# cpu.net
KiCad netlist of a schematic drawn in Altium Designer
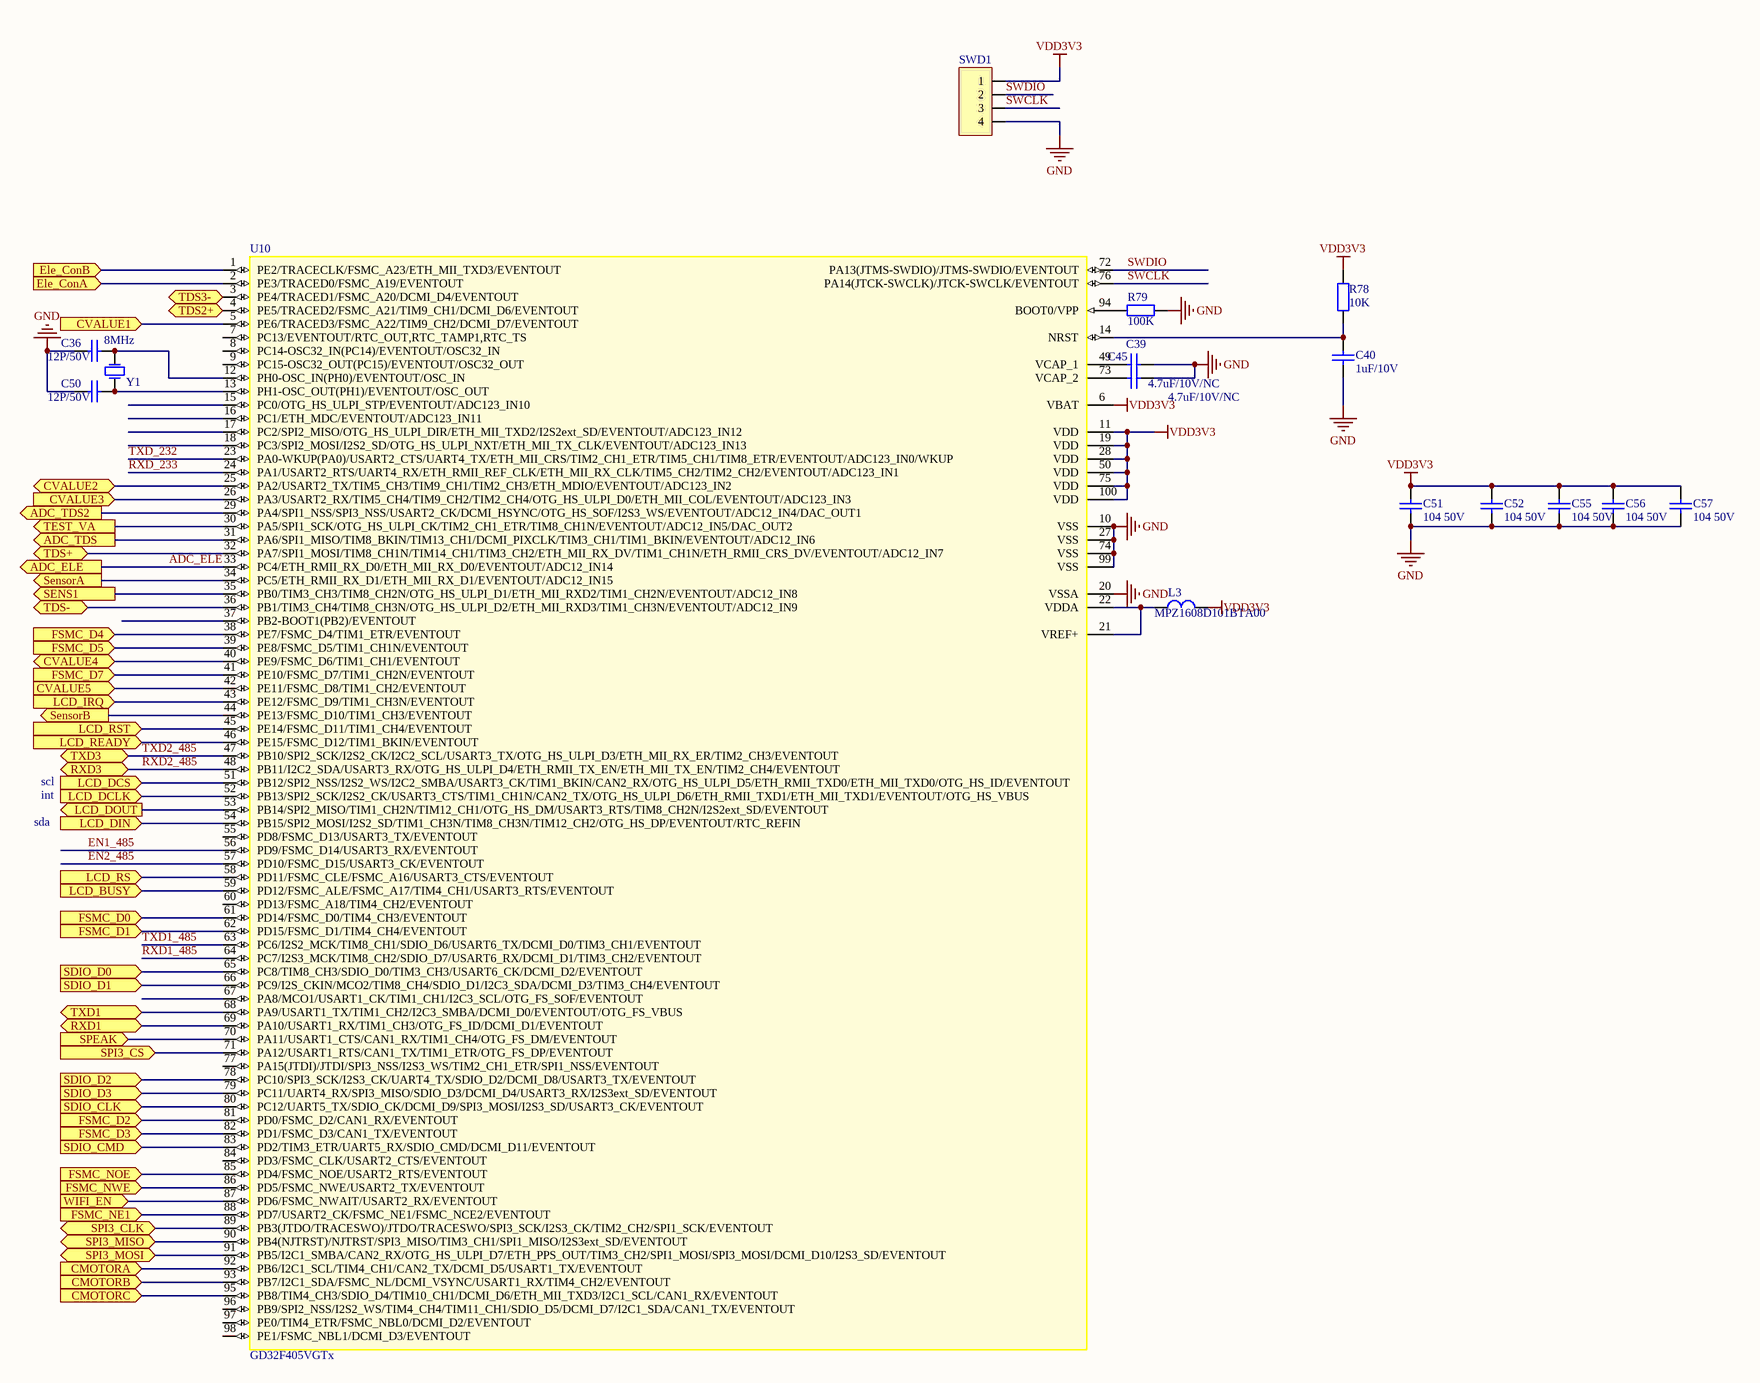
[diagram p0: cpu.SchDoc]

(export (version "E")
  (design (tool "Eeschema 10.0.6"))
  (components
    (comp (ref "C36")
      (value "12P/50V")
      (footprint "SMD-0603C")
      (description "贴片电容 5%")
      (libsource (lib "XiaoyI") (part "CAP4"))
    )
    (comp (ref "C39")
      (value "4.7uF/10V/NC")
      (footprint "SMD-0603C")
      (description "贴片电容 20%")
      (libsource (lib "XiaoyI") (part "CAP4"))
    )
    (comp (ref "C40")
      (value "1uF/10V")
      (footprint "SMD-0603C")
      (description "贴片电容 20%")
      (libsource (lib "XiaoyI") (part "CAP4"))
    )
    (comp (ref "C45")
      (value "4.7uF/10V/NC")
      (footprint "SMD-0603C")
      (description "贴片电容 20%")
      (libsource (lib "XiaoyI") (part "CAP4"))
    )
    (comp (ref "C50")
      (value "12P/50V")
      (footprint "SMD-0603C")
      (description "贴片电容 5%")
      (libsource (lib "XiaoyI") (part "CAP4"))
    )
    (comp (ref "C51")
      (value "104 50V")
      (footprint "SMD-0603C")
      (description "贴片电容 20%")
      (libsource (lib "XiaoyI") (part "CAP4"))
    )
    (comp (ref "C52")
      (value "104 50V")
      (footprint "SMD-0603C")
      (description "贴片电容 20%")
      (libsource (lib "XiaoyI") (part "CAP4"))
    )
    (comp (ref "C55")
      (value "104 50V")
      (footprint "SMD-0603C")
      (description "贴片电容 20%")
      (libsource (lib "XiaoyI") (part "CAP4"))
    )
    (comp (ref "C56")
      (value "104 50V")
      (footprint "SMD-0603C")
      (description "贴片电容 20%")
      (libsource (lib "XiaoyI") (part "CAP4"))
    )
    (comp (ref "C57")
      (value "104 50V")
      (footprint "SMD-0603C")
      (description "贴片电容 20%")
      (libsource (lib "XiaoyI") (part "CAP4"))
    )
    (comp (ref "L3")
      (value "MPZ1608D101BTA00")
      (footprint "SMD-0603")
      (description "磁珠电感 100R 100MHz")
      (libsource (lib "XiaoyI") (part "CIZHU1"))
    )
    (comp (ref "R78")
      (value "10K")
      (footprint "SMD-0603")
      (description "贴片电阻 5%")
      (libsource (lib "") (part "RES2_1"))
    )
    (comp (ref "R79")
      (value "100K")
      (footprint "SMD-0603")
      (description "贴片电阻 5%")
      (libsource (lib "XiaoyI") (part "RES2"))
    )
    (comp (ref "SWD1")
      (value "SIP-4 (NC)")
      (footprint "SIP-4")
      (description "ISP 下载")
      (libsource (lib "XiaoyI") (part "SIP-4"))
    )
    (comp (ref "U10")
      (value "GD32F405VGTx")
      (footprint "STM-LQFP100_N")
      (fields (field (name "MANUFACTURER") "STMicroelectronics") (field (name "PARTNUMBER") "STM32F405VGT6"))
      (libsource (lib "STM32F4") (part "STM32F405VGTx"))
    )
    (comp (ref "Y1")
      (value "8MHz")
      (footprint "XTAL-3225-2")
      (description "3225 贴片晶振")
      (libsource (lib "XiaoyI") (part "XTAL"))
    )
  )
  (nets
    (net (code "1") (name "/ADC_ELE") (class "Default")
      (node (ref "U10") (pin "33") (pinfunction "PC4/ETH_RMII_RX_D0/ETH_MII_RX_D0/EVENTOUT/ADC12_IN14_33") (pintype "bidirectional"))
    )
    (net (code "2") (name "/ADC_TDS") (class "Default")
      (node (ref "U10") (pin "31") (pinfunction "PA6/SPI1_MISO/TIM8_BKIN/TIM13_CH1/DCMI_PIXCLK/TIM3_CH1/TIM1_BKIN/EVENTOUT/ADC12_IN6_31") (pintype "bidirectional"))
    )
    (net (code "3") (name "/ADC_TDS2") (class "Default")
      (node (ref "U10") (pin "29") (pinfunction "PA4/SPI1_NSS/SPI3_NSS/USART2_CK/DCMI_HSYNC/OTG_HS_SOF/I2S3_WS/EVENTOUT/ADC12_IN4/DAC_OUT1_29") (pintype "bidirectional"))
    )
    (net (code "4") (name "/CMOTORA") (class "Default")
      (node (ref "U10") (pin "92") (pinfunction "PB6/I2C1_SCL/TIM4_CH1/CAN2_TX/DCMI_D5/USART1_TX/EVENTOUT_92") (pintype "bidirectional"))
    )
    (net (code "5") (name "/CMOTORB") (class "Default")
      (node (ref "U10") (pin "93") (pinfunction "PB7/I2C1_SDA/FSMC_NL/DCMI_VSYNC/USART1_RX/TIM4_CH2/EVENTOUT_93") (pintype "bidirectional"))
    )
    (net (code "6") (name "/CMOTORC") (class "Default")
      (node (ref "U10") (pin "95") (pinfunction "PB8/TIM4_CH3/SDIO_D4/TIM10_CH1/DCMI_D6/ETH_MII_TXD3/I2C1_SCL/CAN1_RX/EVENTOUT_95") (pintype "bidirectional"))
    )
    (net (code "7") (name "/CVALUE1") (class "Default")
      (node (ref "U10") (pin "5") (pinfunction "PE6/TRACED3/FSMC_A22/TIM9_CH2/DCMI_D7/EVENTOUT_5") (pintype "bidirectional"))
    )
    (net (code "8") (name "/CVALUE2") (class "Default")
      (node (ref "U10") (pin "25") (pinfunction "PA2/USART2_TX/TIM5_CH3/TIM9_CH1/TIM2_CH3/ETH_MDIO/EVENTOUT/ADC123_IN2_25") (pintype "bidirectional"))
    )
    (net (code "9") (name "/CVALUE3") (class "Default")
      (node (ref "U10") (pin "26") (pinfunction "PA3/USART2_RX/TIM5_CH4/TIM9_CH2/TIM2_CH4/OTG_HS_ULPI_D0/ETH_MII_COL/EVENTOUT/ADC123_IN3_26") (pintype "bidirectional"))
    )
    (net (code "10") (name "/CVALUE4") (class "Default")
      (node (ref "U10") (pin "40") (pinfunction "PE9/FSMC_D6/TIM1_CH1/EVENTOUT_40") (pintype "bidirectional"))
    )
    (net (code "11") (name "/CVALUE5") (class "Default")
      (node (ref "U10") (pin "42") (pinfunction "PE11/FSMC_D8/TIM1_CH2/EVENTOUT_42") (pintype "bidirectional"))
    )
    (net (code "12") (name "/EN1_485") (class "Default")
      (node (ref "U10") (pin "56") (pinfunction "PD9/FSMC_D14/USART3_RX/EVENTOUT_56") (pintype "bidirectional"))
    )
    (net (code "13") (name "/EN2_485") (class "Default")
      (node (ref "U10") (pin "57") (pinfunction "PD10/FSMC_D15/USART3_CK/EVENTOUT_57") (pintype "bidirectional"))
    )
    (net (code "14") (name "/Ele_ConA") (class "Default")
      (node (ref "U10") (pin "2") (pinfunction "PE3/TRACED0/FSMC_A19/EVENTOUT_2") (pintype "bidirectional"))
    )
    (net (code "15") (name "/Ele_ConB") (class "Default")
      (node (ref "U10") (pin "1") (pinfunction "PE2/TRACECLK/FSMC_A23/ETH_MII_TXD3/EVENTOUT_1") (pintype "bidirectional"))
    )
    (net (code "16") (name "/FSMC_D0") (class "Default")
      (node (ref "U10") (pin "61") (pinfunction "PD14/FSMC_D0/TIM4_CH3/EVENTOUT_61") (pintype "bidirectional"))
    )
    (net (code "17") (name "/FSMC_D1") (class "Default")
      (node (ref "U10") (pin "62") (pinfunction "PD15/FSMC_D1/TIM4_CH4/EVENTOUT_62") (pintype "bidirectional"))
    )
    (net (code "18") (name "/FSMC_D2") (class "Default")
      (node (ref "U10") (pin "81") (pinfunction "PD0/FSMC_D2/CAN1_RX/EVENTOUT_81") (pintype "bidirectional"))
    )
    (net (code "19") (name "/FSMC_D3") (class "Default")
      (node (ref "U10") (pin "82") (pinfunction "PD1/FSMC_D3/CAN1_TX/EVENTOUT_82") (pintype "bidirectional"))
    )
    (net (code "20") (name "/FSMC_D4") (class "Default")
      (node (ref "U10") (pin "38") (pinfunction "PE7/FSMC_D4/TIM1_ETR/EVENTOUT_38") (pintype "bidirectional"))
    )
    (net (code "21") (name "/FSMC_D5") (class "Default")
      (node (ref "U10") (pin "39") (pinfunction "PE8/FSMC_D5/TIM1_CH1N/EVENTOUT_39") (pintype "bidirectional"))
    )
    (net (code "22") (name "/FSMC_D7") (class "Default")
      (node (ref "U10") (pin "41") (pinfunction "PE10/FSMC_D7/TIM1_CH2N/EVENTOUT_41") (pintype "bidirectional"))
    )
    (net (code "23") (name "/FSMC_NE1") (class "Default")
      (node (ref "U10") (pin "88") (pinfunction "PD7/USART2_CK/FSMC_NE1/FSMC_NCE2/EVENTOUT_88") (pintype "bidirectional"))
    )
    (net (code "24") (name "/FSMC_NOE") (class "Default")
      (node (ref "U10") (pin "85") (pinfunction "PD4/FSMC_NOE/USART2_RTS/EVENTOUT_85") (pintype "bidirectional"))
    )
    (net (code "25") (name "/FSMC_NWE") (class "Default")
      (node (ref "U10") (pin "86") (pinfunction "PD5/FSMC_NWE/USART2_TX/EVENTOUT_86") (pintype "bidirectional"))
    )
    (net (code "26") (name "/LCD_BUSY") (class "Default")
      (node (ref "U10") (pin "59") (pinfunction "PD12/FSMC_ALE/FSMC_A17/TIM4_CH1/USART3_RTS/EVENTOUT_59") (pintype "bidirectional"))
    )
    (net (code "27") (name "/LCD_DCLK") (class "Default")
      (node (ref "U10") (pin "52") (pinfunction "PB13/SPI2_SCK/I2S2_CK/USART3_CTS/TIM1_CH1N/CAN2_TX/OTG_HS_ULPI_D6/ETH_RMII_TXD1/ETH_MII_TXD1/EVENTOUT/OTG_HS_VBUS_52") (pintype "bidirectional"))
    )
    (net (code "28") (name "/LCD_DCS") (class "Default")
      (node (ref "U10") (pin "51") (pinfunction "PB12/SPI2_NSS/I2S2_WS/I2C2_SMBA/USART3_CK/TIM1_BKIN/CAN2_RX/OTG_HS_ULPI_D5/ETH_RMII_TXD0/ETH_MII_TXD0/OTG_HS_ID/EVENTOUT_51") (pintype "bidirectional"))
    )
    (net (code "29") (name "/LCD_DIN") (class "Default")
      (node (ref "U10") (pin "54") (pinfunction "PB15/SPI2_MOSI/I2S2_SD/TIM1_CH3N/TIM8_CH3N/TIM12_CH2/OTG_HS_DP/EVENTOUT/RTC_REFIN_54") (pintype "bidirectional"))
    )
    (net (code "30") (name "/LCD_DOUT") (class "Default")
      (node (ref "U10") (pin "53") (pinfunction "PB14/SPI2_MISO/TIM1_CH2N/TIM12_CH1/OTG_HS_DM/USART3_RTS/TIM8_CH2N/I2S2ext_SD/EVENTOUT_53") (pintype "bidirectional"))
    )
    (net (code "31") (name "/LCD_IRQ") (class "Default")
      (node (ref "U10") (pin "43") (pinfunction "PE12/FSMC_D9/TIM1_CH3N/EVENTOUT_43") (pintype "bidirectional"))
    )
    (net (code "32") (name "/LCD_READY") (class "Default")
      (node (ref "U10") (pin "46") (pinfunction "PE15/FSMC_D12/TIM1_BKIN/EVENTOUT_46") (pintype "bidirectional"))
    )
    (net (code "33") (name "/LCD_RS") (class "Default")
      (node (ref "U10") (pin "58") (pinfunction "PD11/FSMC_CLE/FSMC_A16/USART3_CTS/EVENTOUT_58") (pintype "bidirectional"))
    )
    (net (code "34") (name "/LCD_RST") (class "Default")
      (node (ref "U10") (pin "45") (pinfunction "PE14/FSMC_D11/TIM1_CH4/EVENTOUT_45") (pintype "bidirectional"))
    )
    (net (code "35") (name "/RXD1") (class "Default")
      (node (ref "U10") (pin "69") (pinfunction "PA10/USART1_RX/TIM1_CH3/OTG_FS_ID/DCMI_D1/EVENTOUT_69") (pintype "bidirectional"))
    )
    (net (code "36") (name "/RXD1_485") (class "Default")
      (node (ref "U10") (pin "64") (pinfunction "PC7/I2S3_MCK/TIM8_CH2/SDIO_D7/USART6_RX/DCMI_D1/TIM3_CH2/EVENTOUT_64") (pintype "bidirectional"))
    )
    (net (code "37") (name "/RXD2_485") (class "Default")
      (node (ref "U10") (pin "48") (pinfunction "PB11/I2C2_SDA/USART3_RX/OTG_HS_ULPI_D4/ETH_RMII_TX_EN/ETH_MII_TX_EN/TIM2_CH4/EVENTOUT_48") (pintype "bidirectional"))
    )
    (net (code "38") (name "/RXD_233") (class "Default")
      (node (ref "U10") (pin "24") (pinfunction "PA1/USART2_RTS/UART4_RX/ETH_RMII_REF_CLK/ETH_MII_RX_CLK/TIM5_CH2/TIM2_CH2/EVENTOUT/ADC123_IN1_24") (pintype "bidirectional"))
    )
    (net (code "39") (name "/SDIO_CLK") (class "Default")
      (node (ref "U10") (pin "80") (pinfunction "PC12/UART5_TX/SDIO_CK/DCMI_D9/SPI3_MOSI/I2S3_SD/USART3_CK/EVENTOUT_80") (pintype "bidirectional"))
    )
    (net (code "40") (name "/SDIO_CMD") (class "Default")
      (node (ref "U10") (pin "83") (pinfunction "PD2/TIM3_ETR/UART5_RX/SDIO_CMD/DCMI_D11/EVENTOUT_83") (pintype "bidirectional"))
    )
    (net (code "41") (name "/SDIO_D0") (class "Default")
      (node (ref "U10") (pin "65") (pinfunction "PC8/TIM8_CH3/SDIO_D0/TIM3_CH3/USART6_CK/DCMI_D2/EVENTOUT_65") (pintype "bidirectional"))
    )
    (net (code "42") (name "/SDIO_D1") (class "Default")
      (node (ref "U10") (pin "66") (pinfunction "PC9/I2S_CKIN/MCO2/TIM8_CH4/SDIO_D1/I2C3_SDA/DCMI_D3/TIM3_CH4/EVENTOUT_66") (pintype "bidirectional"))
    )
    (net (code "43") (name "/SDIO_D2") (class "Default")
      (node (ref "U10") (pin "78") (pinfunction "PC10/SPI3_SCK/I2S3_CK/UART4_TX/SDIO_D2/DCMI_D8/USART3_TX/EVENTOUT_78") (pintype "bidirectional"))
    )
    (net (code "44") (name "/SDIO_D3") (class "Default")
      (node (ref "U10") (pin "79") (pinfunction "PC11/UART4_RX/SPI3_MISO/SDIO_D3/DCMI_D4/USART3_RX/I2S3ext_SD/EVENTOUT_79") (pintype "bidirectional"))
    )
    (net (code "45") (name "/SENS1") (class "Default")
      (node (ref "U10") (pin "35") (pinfunction "PB0/TIM3_CH3/TIM8_CH2N/OTG_HS_ULPI_D1/ETH_MII_RXD2/TIM1_CH2N/EVENTOUT/ADC12_IN8_35") (pintype "bidirectional"))
    )
    (net (code "46") (name "/SPEAK") (class "Default")
      (node (ref "U10") (pin "70") (pinfunction "PA11/USART1_CTS/CAN1_RX/TIM1_CH4/OTG_FS_DM/EVENTOUT_70") (pintype "bidirectional"))
    )
    (net (code "47") (name "/SPI3_CLK") (class "Default")
      (node (ref "U10") (pin "89") (pinfunction "PB3(JTDO/TRACESWO)/JTDO/TRACESWO/SPI3_SCK/I2S3_CK/TIM2_CH2/SPI1_SCK/EVENTOUT_89") (pintype "bidirectional"))
    )
    (net (code "48") (name "/SPI3_CS") (class "Default")
      (node (ref "U10") (pin "71") (pinfunction "PA12/USART1_RTS/CAN1_TX/TIM1_ETR/OTG_FS_DP/EVENTOUT_71") (pintype "bidirectional"))
    )
    (net (code "49") (name "/SPI3_MISO") (class "Default")
      (node (ref "U10") (pin "90") (pinfunction "PB4(NJTRST)/NJTRST/SPI3_MISO/TIM3_CH1/SPI1_MISO/I2S3ext_SD/EVENTOUT_90") (pintype "bidirectional"))
    )
    (net (code "50") (name "/SPI3_MOSI") (class "Default")
      (node (ref "U10") (pin "91") (pinfunction "PB5/I2C1_SMBA/CAN2_RX/OTG_HS_ULPI_D7/ETH_PPS_OUT/TIM3_CH2/SPI1_MOSI/SPI3_MOSI/DCMI_D10/I2S3_SD/EVENTOUT_91") (pintype "bidirectional"))
    )
    (net (code "51") (name "/SWCLK") (class "Default")
      (node (ref "SWD1") (pin "3") (pinfunction "3_3") (pintype "passive"))
      (node (ref "U10") (pin "76") (pinfunction "PA14(JTCK-SWCLK)/JTCK-SWCLK/EVENTOUT_76") (pintype "bidirectional"))
    )
    (net (code "52") (name "/SWDIO") (class "Default")
      (node (ref "SWD1") (pin "2") (pinfunction "2_2") (pintype "passive"))
      (node (ref "U10") (pin "72") (pinfunction "PA13(JTMS-SWDIO)/JTMS-SWDIO/EVENTOUT_72") (pintype "bidirectional"))
    )
    (net (code "53") (name "/SensorA") (class "Default")
      (node (ref "U10") (pin "34") (pinfunction "PC5/ETH_RMII_RX_D1/ETH_MII_RX_D1/EVENTOUT/ADC12_IN15_34") (pintype "bidirectional"))
    )
    (net (code "54") (name "/SensorB") (class "Default")
      (node (ref "U10") (pin "44") (pinfunction "PE13/FSMC_D10/TIM1_CH3/EVENTOUT_44") (pintype "bidirectional"))
    )
    (net (code "55") (name "/TDS+") (class "Default")
      (node (ref "U10") (pin "32") (pinfunction "PA7/SPI1_MOSI/TIM8_CH1N/TIM14_CH1/TIM3_CH2/ETH_MII_RX_DV/TIM1_CH1N/ETH_RMII_CRS_DV/EVENTOUT/ADC12_IN7_32") (pintype "bidirectional"))
    )
    (net (code "56") (name "/TDS-") (class "Default")
      (node (ref "U10") (pin "36") (pinfunction "PB1/TIM3_CH4/TIM8_CH3N/OTG_HS_ULPI_D2/ETH_MII_RXD3/TIM1_CH3N/EVENTOUT/ADC12_IN9_36") (pintype "bidirectional"))
    )
    (net (code "57") (name "/TDS2+") (class "Default")
      (node (ref "U10") (pin "4") (pinfunction "PE5/TRACED2/FSMC_A21/TIM9_CH1/DCMI_D6/EVENTOUT_4") (pintype "bidirectional"))
    )
    (net (code "58") (name "/TDS3-") (class "Default")
      (node (ref "U10") (pin "3") (pinfunction "PE4/TRACED1/FSMC_A20/DCMI_D4/EVENTOUT_3") (pintype "bidirectional"))
    )
    (net (code "59") (name "/TEST_VA") (class "Default")
      (node (ref "U10") (pin "30") (pinfunction "PA5/SPI1_SCK/OTG_HS_ULPI_CK/TIM2_CH1_ETR/TIM8_CH1N/EVENTOUT/ADC12_IN5/DAC_OUT2_30") (pintype "bidirectional"))
    )
    (net (code "60") (name "/TXD1") (class "Default")
      (node (ref "U10") (pin "68") (pinfunction "PA9/USART1_TX/TIM1_CH2/I2C3_SMBA/DCMI_D0/EVENTOUT/OTG_FS_VBUS_68") (pintype "bidirectional"))
    )
    (net (code "61") (name "/TXD1_485") (class "Default")
      (node (ref "U10") (pin "63") (pinfunction "PC6/I2S2_MCK/TIM8_CH1/SDIO_D6/USART6_TX/DCMI_D0/TIM3_CH1/EVENTOUT_63") (pintype "bidirectional"))
    )
    (net (code "62") (name "/TXD2_485") (class "Default")
      (node (ref "U10") (pin "47") (pinfunction "PB10/SPI2_SCK/I2S2_CK/I2C2_SCL/USART3_TX/OTG_HS_ULPI_D3/ETH_MII_RX_ER/TIM2_CH3/EVENTOUT_47") (pintype "bidirectional"))
    )
    (net (code "63") (name "/TXD_232") (class "Default")
      (node (ref "U10") (pin "23") (pinfunction "PA0-WKUP(PA0)/USART2_CTS/UART4_TX/ETH_MII_CRS/TIM2_CH1_ETR/TIM5_CH1/TIM8_ETR/EVENTOUT/ADC123_IN0/WKUP_23") (pintype "bidirectional"))
    )
    (net (code "64") (name "/WIFI_EN") (class "Default")
      (node (ref "U10") (pin "87") (pinfunction "PD6/FSMC_NWAIT/USART2_RX/EVENTOUT_87") (pintype "bidirectional"))
    )
    (net (code "65") (name "GND") (class "Default")
      (node (ref "C36") (pin "2") (pinfunction "2_2") (pintype "passive"))
      (node (ref "C39") (pin "1") (pinfunction "1_1") (pintype "passive"))
      (node (ref "C40") (pin "1") (pinfunction "1_1") (pintype "passive"))
      (node (ref "C45") (pin "1") (pinfunction "1_1") (pintype "passive"))
      (node (ref "C50") (pin "2") (pinfunction "2_2") (pintype "passive"))
      (node (ref "C51") (pin "1") (pinfunction "1_1") (pintype "passive"))
      (node (ref "C52") (pin "1") (pinfunction "1_1") (pintype "passive"))
      (node (ref "C55") (pin "1") (pinfunction "1_1") (pintype "passive"))
      (node (ref "C56") (pin "1") (pinfunction "1_1") (pintype "passive"))
      (node (ref "C57") (pin "1") (pinfunction "1_1") (pintype "passive"))
      (node (ref "R79") (pin "1") (pinfunction "1_1") (pintype "passive"))
      (node (ref "SWD1") (pin "4") (pinfunction "4_4") (pintype "passive"))
      (node (ref "U10") (pin "10") (pinfunction "VSS_10") (pintype "power_in"))
      (node (ref "U10") (pin "20") (pinfunction "VSSA_20") (pintype "power_in"))
      (node (ref "U10") (pin "27") (pinfunction "VSS_27") (pintype "power_in"))
      (node (ref "U10") (pin "74") (pinfunction "VSS_74") (pintype "power_in"))
      (node (ref "U10") (pin "99") (pinfunction "VSS_99") (pintype "power_in"))
    )
    (net (code "66") (name "Net-(U10-BOOT0{slash}VPP)") (class "Default")
      (node (ref "R79") (pin "2") (pinfunction "2_2") (pintype "passive"))
      (node (ref "U10") (pin "94") (pinfunction "BOOT0/VPP_94") (pintype "input"))
    )
    (net (code "67") (name "Net-(U10-NRST)") (class "Default")
      (node (ref "C40") (pin "2") (pinfunction "2_2") (pintype "passive"))
      (node (ref "R78") (pin "1") (pinfunction "1_1") (pintype "passive"))
      (node (ref "U10") (pin "14") (pinfunction "NRST_14") (pintype "bidirectional"))
    )
    (net (code "68") (name "Net-(U10-PH0-OSC_IN(PH0){slash}EVENTOUT{slash}OSC_IN)") (class "Default")
      (node (ref "C36") (pin "1") (pinfunction "1_1") (pintype "passive"))
      (node (ref "U10") (pin "12") (pinfunction "PH0-OSC_IN(PH0)/EVENTOUT/OSC_IN_12") (pintype "bidirectional"))
      (node (ref "Y1") (pin "2") (pinfunction "OSC2_2") (pintype "passive"))
    )
    (net (code "69") (name "Net-(U10-PH1-OSC_OUT(PH1){slash}EVENTOUT{slash}OSC_OUT)") (class "Default")
      (node (ref "C50") (pin "1") (pinfunction "1_1") (pintype "passive"))
      (node (ref "U10") (pin "13") (pinfunction "PH1-OSC_OUT(PH1)/EVENTOUT/OSC_OUT_13") (pintype "bidirectional"))
      (node (ref "Y1") (pin "1") (pinfunction "OSC1_1") (pintype "passive"))
    )
    (net (code "70") (name "Net-(U10-VCAP_1)") (class "Default")
      (node (ref "C39") (pin "2") (pinfunction "2_2") (pintype "passive"))
      (node (ref "U10") (pin "49") (pinfunction "VCAP_1_49") (pintype "power_in"))
    )
    (net (code "71") (name "Net-(U10-VCAP_2)") (class "Default")
      (node (ref "C45") (pin "2") (pinfunction "2_2") (pintype "passive"))
      (node (ref "U10") (pin "73") (pinfunction "VCAP_2_73") (pintype "power_in"))
    )
    (net (code "72") (name "Net-(U10-VDDA)") (class "Default")
      (node (ref "L3") (pin "2") (pinfunction "2_2") (pintype "passive"))
      (node (ref "U10") (pin "21") (pinfunction "VREF+_21") (pintype "power_in"))
      (node (ref "U10") (pin "22") (pinfunction "VDDA_22") (pintype "power_in"))
    )
    (net (code "73") (name "VDD3V3") (class "Default")
      (node (ref "C51") (pin "2") (pinfunction "2_2") (pintype "passive"))
      (node (ref "C52") (pin "2") (pinfunction "2_2") (pintype "passive"))
      (node (ref "C55") (pin "2") (pinfunction "2_2") (pintype "passive"))
      (node (ref "C56") (pin "2") (pinfunction "2_2") (pintype "passive"))
      (node (ref "C57") (pin "2") (pinfunction "2_2") (pintype "passive"))
      (node (ref "L3") (pin "1") (pinfunction "1_1") (pintype "passive"))
      (node (ref "R78") (pin "2") (pinfunction "2_2") (pintype "passive"))
      (node (ref "SWD1") (pin "1") (pinfunction "1_1") (pintype "passive"))
      (node (ref "U10") (pin "100") (pinfunction "VDD_100") (pintype "power_in"))
      (node (ref "U10") (pin "11") (pinfunction "VDD_11") (pintype "power_in"))
      (node (ref "U10") (pin "19") (pinfunction "VDD_19") (pintype "power_in"))
      (node (ref "U10") (pin "28") (pinfunction "VDD_28") (pintype "power_in"))
      (node (ref "U10") (pin "50") (pinfunction "VDD_50") (pintype "power_in"))
      (node (ref "U10") (pin "6") (pinfunction "VBAT_6") (pintype "power_in"))
      (node (ref "U10") (pin "75") (pinfunction "VDD_75") (pintype "power_in"))
    )
    (net (code "74") (name "unconnected-(U10-PA8{slash}MCO1{slash}USART1_CK{slash}TIM1_CH1{slash}I2C3_SCL{slash}OTG_FS_SOF{slash}EVENTOUT-Pad67)") (class "Default")
      (node (ref "U10") (pin "67") (pinfunction "PA8/MCO1/USART1_CK/TIM1_CH1/I2C3_SCL/OTG_FS_SOF/EVENTOUT_67") (pintype "bidirectional"))
    )
    (net (code "75") (name "unconnected-(U10-PA15(JTDI){slash}JTDI{slash}SPI3_NSS{slash}I2S3_WS{slash}TIM2_CH1_ETR{slash}SPI1_NSS{slash}EVENTOUT-Pad77)") (class "Default")
      (node (ref "U10") (pin "77") (pinfunction "PA15(JTDI)/JTDI/SPI3_NSS/I2S3_WS/TIM2_CH1_ETR/SPI1_NSS/EVENTOUT_77") (pintype "bidirectional"))
    )
    (net (code "76") (name "unconnected-(U10-PB2-BOOT1(PB2){slash}EVENTOUT-Pad37)") (class "Default")
      (node (ref "U10") (pin "37") (pinfunction "PB2-BOOT1(PB2)/EVENTOUT_37") (pintype "bidirectional"))
    )
    (net (code "77") (name "unconnected-(U10-PB9{slash}SPI2_NSS{slash}I2S2_WS{slash}TIM4_CH4{slash}TIM11_CH1{slash}SDIO_D5{slash}DCMI_D7{slash}I2C1_SDA{slash}CAN1_TX{slash}EVENTOUT-Pad96)") (class "Default")
      (node (ref "U10") (pin "96") (pinfunction "PB9/SPI2_NSS/I2S2_WS/TIM4_CH4/TIM11_CH1/SDIO_D5/DCMI_D7/I2C1_SDA/CAN1_TX/EVENTOUT_96") (pintype "bidirectional"))
    )
    (net (code "78") (name "unconnected-(U10-PC0{slash}OTG_HS_ULPI_STP{slash}EVENTOUT{slash}ADC123_IN10-Pad15)") (class "Default")
      (node (ref "U10") (pin "15") (pinfunction "PC0/OTG_HS_ULPI_STP/EVENTOUT/ADC123_IN10_15") (pintype "bidirectional"))
    )
    (net (code "79") (name "unconnected-(U10-PC1{slash}ETH_MDC{slash}EVENTOUT{slash}ADC123_IN11-Pad16)") (class "Default")
      (node (ref "U10") (pin "16") (pinfunction "PC1/ETH_MDC/EVENTOUT/ADC123_IN11_16") (pintype "bidirectional"))
    )
    (net (code "80") (name "unconnected-(U10-PC2{slash}SPI2_MISO{slash}OTG_HS_ULPI_DIR{slash}ETH_MII_TXD2{slash}I2S2ext_SD{slash}EVENTOUT{slash}ADC123_IN12-Pad17)") (class "Default")
      (node (ref "U10") (pin "17") (pinfunction "PC2/SPI2_MISO/OTG_HS_ULPI_DIR/ETH_MII_TXD2/I2S2ext_SD/EVENTOUT/ADC123_IN12_17") (pintype "bidirectional"))
    )
    (net (code "81") (name "unconnected-(U10-PC3{slash}SPI2_MOSI{slash}I2S2_SD{slash}OTG_HS_ULPI_NXT{slash}ETH_MII_TX_CLK{slash}EVENTOUT{slash}ADC123_IN13-Pad18)") (class "Default")
      (node (ref "U10") (pin "18") (pinfunction "PC3/SPI2_MOSI/I2S2_SD/OTG_HS_ULPI_NXT/ETH_MII_TX_CLK/EVENTOUT/ADC123_IN13_18") (pintype "bidirectional"))
    )
    (net (code "82") (name "unconnected-(U10-PC13{slash}EVENTOUT{slash}RTC_OUT,RTC_TAMP1,RTC_TS-Pad7)") (class "Default")
      (node (ref "U10") (pin "7") (pinfunction "PC13/EVENTOUT/RTC_OUT,RTC_TAMP1,RTC_TS_7") (pintype "bidirectional"))
    )
    (net (code "83") (name "unconnected-(U10-PC14-OSC32_IN(PC14){slash}EVENTOUT{slash}OSC32_IN-Pad8)") (class "Default")
      (node (ref "U10") (pin "8") (pinfunction "PC14-OSC32_IN(PC14)/EVENTOUT/OSC32_IN_8") (pintype "bidirectional"))
    )
    (net (code "84") (name "unconnected-(U10-PC15-OSC32_OUT(PC15){slash}EVENTOUT{slash}OSC32_OUT-Pad9)") (class "Default")
      (node (ref "U10") (pin "9") (pinfunction "PC15-OSC32_OUT(PC15)/EVENTOUT/OSC32_OUT_9") (pintype "bidirectional"))
    )
    (net (code "85") (name "unconnected-(U10-PD3{slash}FSMC_CLK{slash}USART2_CTS{slash}EVENTOUT-Pad84)") (class "Default")
      (node (ref "U10") (pin "84") (pinfunction "PD3/FSMC_CLK/USART2_CTS/EVENTOUT_84") (pintype "bidirectional"))
    )
    (net (code "86") (name "unconnected-(U10-PD8{slash}FSMC_D13{slash}USART3_TX{slash}EVENTOUT-Pad55)") (class "Default")
      (node (ref "U10") (pin "55") (pinfunction "PD8/FSMC_D13/USART3_TX/EVENTOUT_55") (pintype "bidirectional"))
    )
    (net (code "87") (name "unconnected-(U10-PD13{slash}FSMC_A18{slash}TIM4_CH2{slash}EVENTOUT-Pad60)") (class "Default")
      (node (ref "U10") (pin "60") (pinfunction "PD13/FSMC_A18/TIM4_CH2/EVENTOUT_60") (pintype "bidirectional"))
    )
    (net (code "88") (name "unconnected-(U10-PE0{slash}TIM4_ETR{slash}FSMC_NBL0{slash}DCMI_D2{slash}EVENTOUT-Pad97)") (class "Default")
      (node (ref "U10") (pin "97") (pinfunction "PE0/TIM4_ETR/FSMC_NBL0/DCMI_D2/EVENTOUT_97") (pintype "bidirectional"))
    )
    (net (code "89") (name "unconnected-(U10-PE1{slash}FSMC_NBL1{slash}DCMI_D3{slash}EVENTOUT-Pad98)") (class "Default")
      (node (ref "U10") (pin "98") (pinfunction "PE1/FSMC_NBL1/DCMI_D3/EVENTOUT_98") (pintype "bidirectional"))
    )
  )
)
